# l293DC.net
KiCad netlist of a schematic drawn in EAGLE
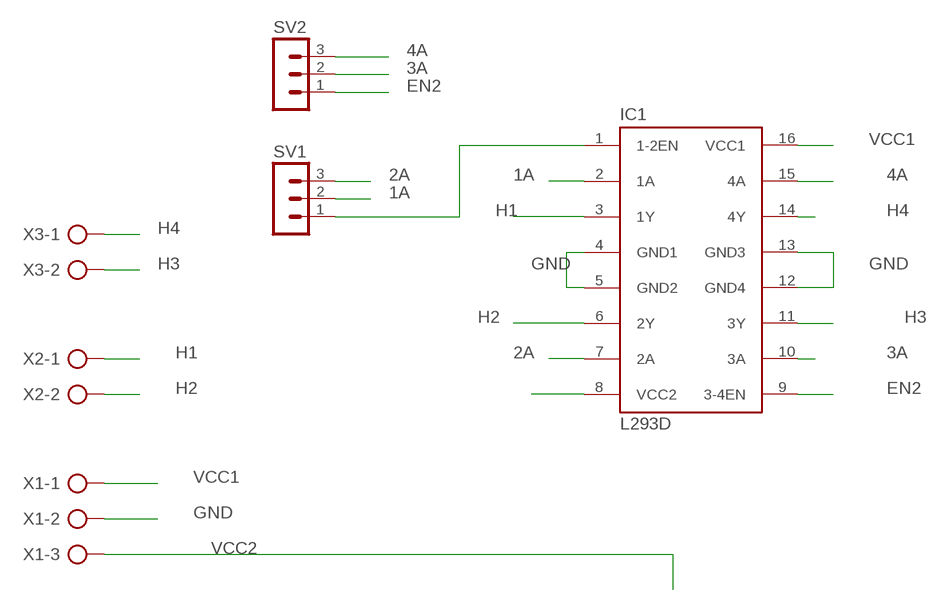
[diagram p0: schematic, sheet 1]

(export (version "E")
  (design (tool "Eeschema 10.0.6"))
  (components
    (comp (ref "IC1")
      (value "L293D")
      (footprint "eagle-import:DIL16")
      (libsource (lib "eagle-import") (part "L293D"))
    )
    (comp (ref "SV1")
      (value "MA03-1")
      (footprint "eagle-import:MA03-1")
      (libsource (lib "eagle-import") (part "MA03-1"))
    )
    (comp (ref "SV2")
      (value "MA03-1")
      (footprint "eagle-import:MA03-1")
      (libsource (lib "eagle-import") (part "MA03-1"))
    )
    (comp (ref "X1")
      (value "AK500/3")
      (footprint "eagle-import:AK500_3")
      (libsource (lib "eagle-import") (part "AK500/3"))
    )
    (comp (ref "X2")
      (value "AK500/2")
      (footprint "eagle-import:AK500_2")
      (libsource (lib "eagle-import") (part "AK500/2"))
    )
    (comp (ref "X3")
      (value "AK500/2")
      (footprint "eagle-import:AK500_2")
      (libsource (lib "eagle-import") (part "AK500/2"))
    )
  )
  (nets
    (net (code "1") (name "/1A") (class "Default")
      (node (ref "IC1") (pin "2") (pinfunction "1A_2") (pintype "input"))
      (node (ref "SV1") (pin "2") (pinfunction "2_2") (pintype "passive"))
    )
    (net (code "2") (name "/2A") (class "Default")
      (node (ref "IC1") (pin "7") (pinfunction "2A_7") (pintype "input"))
      (node (ref "SV1") (pin "3") (pinfunction "3_3") (pintype "passive"))
    )
    (net (code "3") (name "/3A") (class "Default")
      (node (ref "IC1") (pin "10") (pinfunction "3A_10") (pintype "input"))
      (node (ref "SV2") (pin "2") (pinfunction "2_2") (pintype "passive"))
    )
    (net (code "4") (name "/4A") (class "Default")
      (node (ref "IC1") (pin "15") (pinfunction "4A_15") (pintype "input"))
      (node (ref "SV2") (pin "3") (pinfunction "3_3") (pintype "passive"))
    )
    (net (code "5") (name "/EN2") (class "Default")
      (node (ref "IC1") (pin "9") (pinfunction "3-4EN_9") (pintype "input"))
      (node (ref "SV2") (pin "1") (pinfunction "1_1") (pintype "passive"))
    )
    (net (code "6") (name "/GND") (class "Default")
      (node (ref "IC1") (pin "12") (pinfunction "GND4_12") (pintype "power_in"))
      (node (ref "IC1") (pin "13") (pinfunction "GND3_13") (pintype "power_in"))
      (node (ref "IC1") (pin "4") (pinfunction "GND1_4") (pintype "power_in"))
      (node (ref "IC1") (pin "5") (pinfunction "GND2_5") (pintype "power_in"))
      (node (ref "X1") (pin "2") (pinfunction "KL_2") (pintype "passive"))
    )
    (net (code "7") (name "/H1") (class "Default")
      (node (ref "IC1") (pin "3") (pinfunction "1Y_3") (pintype "output"))
      (node (ref "X2") (pin "1") (pinfunction "KL_1") (pintype "passive"))
    )
    (net (code "8") (name "/H2") (class "Default")
      (node (ref "IC1") (pin "6") (pinfunction "2Y_6") (pintype "output"))
      (node (ref "X2") (pin "2") (pinfunction "KL_2") (pintype "passive"))
    )
    (net (code "9") (name "/H3") (class "Default")
      (node (ref "IC1") (pin "11") (pinfunction "3Y_11") (pintype "output"))
      (node (ref "X3") (pin "2") (pinfunction "KL_2") (pintype "passive"))
    )
    (net (code "10") (name "/H4") (class "Default")
      (node (ref "IC1") (pin "14") (pinfunction "4Y_14") (pintype "output"))
      (node (ref "X3") (pin "1") (pinfunction "KL_1") (pintype "passive"))
    )
    (net (code "11") (name "/VCC1") (class "Default")
      (node (ref "IC1") (pin "16") (pinfunction "VCC1_16") (pintype "power_in"))
      (node (ref "X1") (pin "1") (pinfunction "KL_1") (pintype "passive"))
    )
    (net (code "12") (name "/VCC2") (class "Default")
      (node (ref "IC1") (pin "8") (pinfunction "VCC2_8") (pintype "power_in"))
      (node (ref "X1") (pin "3") (pinfunction "KL_3") (pintype "passive"))
    )
    (net (code "13") (name "Net-(IC1-1-2EN)") (class "Default")
      (node (ref "IC1") (pin "1") (pinfunction "1-2EN_1") (pintype "input"))
      (node (ref "SV1") (pin "1") (pinfunction "1_1") (pintype "passive"))
    )
  )
)
